# PCB.net
KiCad netlist of a schematic drawn in EAGLE
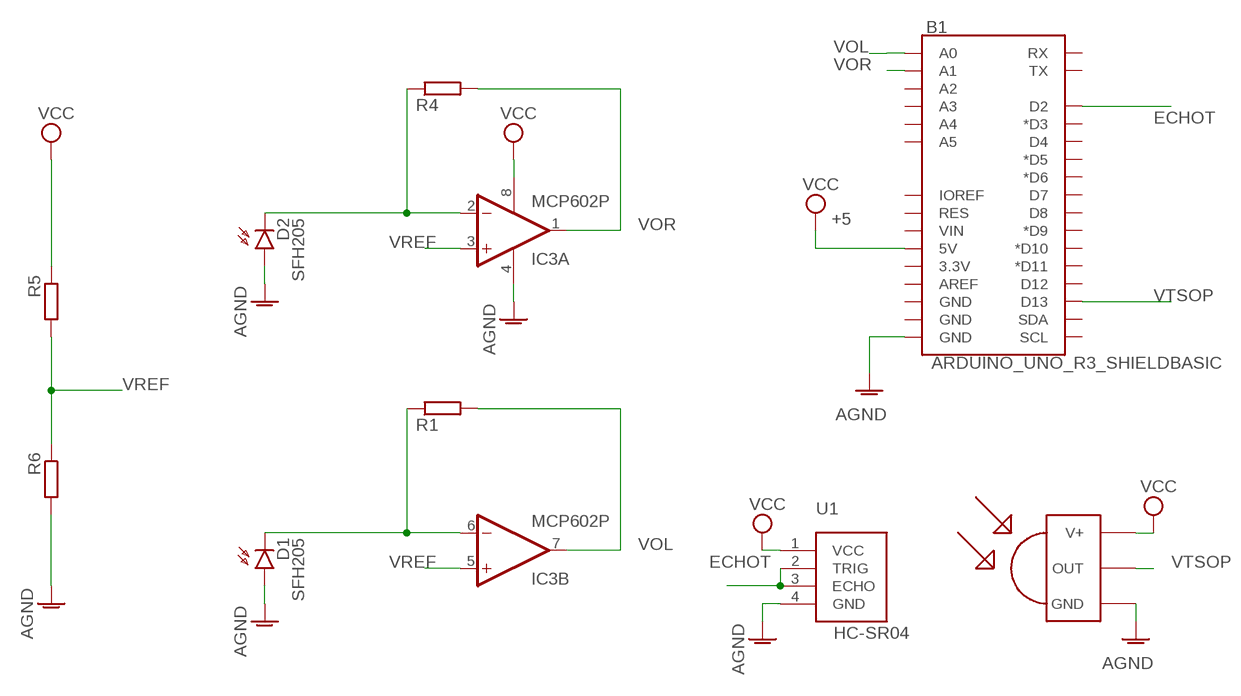
[diagram p0: schematic, sheet 1]

(export (version "E")
  (design (tool "Eeschema 10.0.6"))
  (components
    (comp (ref "B1")
      (value "ARDUINO_UNO_R3_SHIELDBASIC")
      (footprint "eagle-import:UNO_R3_SHIELD")
      (libsource (lib "eagle-import") (part "ARDUINO_UNO_R3_SHIELDBASIC"))
    )
    (comp (ref "D1")
      (value "SFH205")
      (footprint "eagle-import:SFH205")
      (libsource (lib "eagle-import") (part "SFH205"))
    )
    (comp (ref "D2")
      (value "SFH205")
      (footprint "eagle-import:SFH205")
      (libsource (lib "eagle-import") (part "SFH205"))
    )
    (comp (ref "IC3")
      (value "MCP602P")
      (footprint "eagle-import:DIL08")
      (libsource (lib "eagle-import") (part "MCP602P"))
    )
    (comp (ref "R1")
      (value "R-EU_0207/10")
      (footprint "eagle-import:0207_10")
      (libsource (lib "eagle-import") (part "R-EU_0207/10"))
    )
    (comp (ref "R4")
      (value "R-EU_0207/10")
      (footprint "eagle-import:0207_10")
      (libsource (lib "eagle-import") (part "R-EU_0207/10"))
    )
    (comp (ref "R5")
      (value "R-EU_0207/10")
      (footprint "eagle-import:0207_10")
      (libsource (lib "eagle-import") (part "R-EU_0207/10"))
    )
    (comp (ref "R6")
      (value "R-EU_0207/10")
      (footprint "eagle-import:0207_10")
      (libsource (lib "eagle-import") (part "R-EU_0207/10"))
    )
    (comp (ref "U$3")
      (value "TSOP4856")
      (footprint "eagle-import:TSOP18XX")
      (libsource (lib "eagle-import") (part "TSOP4856"))
    )
    (comp (ref "U1")
      (value "HC-SR04")
      (footprint "eagle-import:XCVR_HC-SR04")
      (fields (field (name "MF") "SparkFun Electronics"))
      (libsource (lib "eagle-import") (part "HC-SR04"))
    )
  )
  (nets
    (net (code "1") (name "/ECHOT") (class "Default")
      (node (ref "B1") (pin "D2") (pinfunction "D2_D2") (pintype "bidirectional"))
      (node (ref "U1") (pin "2") (pinfunction "TRIG_2") (pintype "bidirectional"))
      (node (ref "U1") (pin "3") (pinfunction "ECHO_3") (pintype "bidirectional"))
    )
    (net (code "2") (name "/VOL") (class "Default")
      (node (ref "B1") (pin "A0") (pinfunction "A0_A0") (pintype "bidirectional"))
      (node (ref "IC3") (pin "7") (pinfunction "OUT_7") (pintype "output"))
      (node (ref "R1") (pin "2") (pinfunction "2_2") (pintype "passive"))
    )
    (net (code "3") (name "/VOR") (class "Default")
      (node (ref "B1") (pin "A1") (pinfunction "A1_A1") (pintype "bidirectional"))
      (node (ref "IC3") (pin "1") (pinfunction "OUT_1") (pintype "output"))
      (node (ref "R4") (pin "2") (pinfunction "2_2") (pintype "passive"))
    )
    (net (code "4") (name "/VREF") (class "Default")
      (node (ref "IC3") (pin "3") (pinfunction "+IN_3") (pintype "input"))
      (node (ref "IC3") (pin "5") (pinfunction "+IN_5") (pintype "input"))
      (node (ref "R5") (pin "2") (pinfunction "2_2") (pintype "passive"))
      (node (ref "R6") (pin "1") (pinfunction "1_1") (pintype "passive"))
    )
    (net (code "5") (name "/VTSOP") (class "Default")
      (node (ref "B1") (pin "D13") (pinfunction "D13_D13") (pintype "bidirectional"))
      (node (ref "U$3") (pin "OUT") (pinfunction "OUT_OUT") (pintype "bidirectional"))
    )
    (net (code "6") (name "AGND") (class "Default")
      (node (ref "B1") (pin "GND@0") (pinfunction "GND_GND@0") (pintype "bidirectional"))
      (node (ref "D1") (pin "A") (pinfunction "A_A") (pintype "passive"))
      (node (ref "D2") (pin "A") (pinfunction "A_A") (pintype "passive"))
      (node (ref "IC3") (pin "4") (pinfunction "V-_4") (pintype "power_in"))
      (node (ref "R6") (pin "2") (pinfunction "2_2") (pintype "passive"))
      (node (ref "U$3") (pin "GND") (pinfunction "GND_GND") (pintype "bidirectional"))
      (node (ref "U1") (pin "4") (pinfunction "GND_4") (pintype "power_in"))
    )
    (net (code "7") (name "Net-(D1-C)") (class "Default")
      (node (ref "D1") (pin "K") (pinfunction "C_K") (pintype "passive"))
      (node (ref "IC3") (pin "6") (pinfunction "-IN_6") (pintype "input"))
      (node (ref "R1") (pin "1") (pinfunction "1_1") (pintype "passive"))
    )
    (net (code "8") (name "Net-(D2-C)") (class "Default")
      (node (ref "D2") (pin "K") (pinfunction "C_K") (pintype "passive"))
      (node (ref "IC3") (pin "2") (pinfunction "-IN_2") (pintype "input"))
      (node (ref "R4") (pin "1") (pinfunction "1_1") (pintype "passive"))
    )
    (net (code "9") (name "VCC") (class "Default")
      (node (ref "B1") (pin "5V") (pinfunction "5V_5V") (pintype "bidirectional"))
      (node (ref "IC3") (pin "8") (pinfunction "V+_8") (pintype "power_in"))
      (node (ref "R5") (pin "1") (pinfunction "1_1") (pintype "passive"))
      (node (ref "U$3") (pin "VCC") (pinfunction "V+_VCC") (pintype "bidirectional"))
      (node (ref "U1") (pin "1") (pinfunction "VCC_1") (pintype "power_in"))
    )
    (net (code "10") (name "unconnected-(B1-*D3-PadD3)") (class "Default")
      (node (ref "B1") (pin "D3") (pinfunction "*D3_D3") (pintype "bidirectional"))
    )
    (net (code "11") (name "unconnected-(B1-*D5-PadD5)") (class "Default")
      (node (ref "B1") (pin "D5") (pinfunction "*D5_D5") (pintype "bidirectional"))
    )
    (net (code "12") (name "unconnected-(B1-*D6-PadD6)") (class "Default")
      (node (ref "B1") (pin "D6") (pinfunction "*D6_D6") (pintype "bidirectional"))
    )
    (net (code "13") (name "unconnected-(B1-*D9-PadD9)") (class "Default")
      (node (ref "B1") (pin "D9") (pinfunction "*D9_D9") (pintype "bidirectional"))
    )
    (net (code "14") (name "unconnected-(B1-*D10-PadD10)") (class "Default")
      (node (ref "B1") (pin "D10") (pinfunction "*D10_D10") (pintype "bidirectional"))
    )
    (net (code "15") (name "unconnected-(B1-*D11-PadD11)") (class "Default")
      (node (ref "B1") (pin "D11") (pinfunction "*D11_D11") (pintype "bidirectional"))
    )
    (net (code "16") (name "unconnected-(B1-GND-PadGND@1)") (class "Default")
      (node (ref "B1") (pin "GND@1") (pinfunction "GND_GND@1") (pintype "bidirectional"))
    )
    (net (code "17") (name "unconnected-(B1-GND-PadGND@2)") (class "Default")
      (node (ref "B1") (pin "GND@2") (pinfunction "GND_GND@2") (pintype "bidirectional"))
    )
    (net (code "18") (name "unconnected-(B1-Pad3.3V)") (class "Default")
      (node (ref "B1") (pin "3.3V") (pinfunction "3.3V_3.3V") (pintype "bidirectional"))
    )
    (net (code "19") (name "unconnected-(B1-PadA2)") (class "Default")
      (node (ref "B1") (pin "A2") (pinfunction "A2_A2") (pintype "bidirectional"))
    )
    (net (code "20") (name "unconnected-(B1-PadA3)") (class "Default")
      (node (ref "B1") (pin "A3") (pinfunction "A3_A3") (pintype "bidirectional"))
    )
    (net (code "21") (name "unconnected-(B1-PadA4)") (class "Default")
      (node (ref "B1") (pin "A4") (pinfunction "A4_A4") (pintype "bidirectional"))
    )
    (net (code "22") (name "unconnected-(B1-PadA5)") (class "Default")
      (node (ref "B1") (pin "A5") (pinfunction "A5_A5") (pintype "bidirectional"))
    )
    (net (code "23") (name "unconnected-(B1-PadAREF)") (class "Default")
      (node (ref "B1") (pin "AREF") (pinfunction "AREF_AREF") (pintype "bidirectional"))
    )
    (net (code "24") (name "unconnected-(B1-PadD4)") (class "Default")
      (node (ref "B1") (pin "D4") (pinfunction "D4_D4") (pintype "bidirectional"))
    )
    (net (code "25") (name "unconnected-(B1-PadD7)") (class "Default")
      (node (ref "B1") (pin "D7") (pinfunction "D7_D7") (pintype "bidirectional"))
    )
    (net (code "26") (name "unconnected-(B1-PadD8)") (class "Default")
      (node (ref "B1") (pin "D8") (pinfunction "D8_D8") (pintype "bidirectional"))
    )
    (net (code "27") (name "unconnected-(B1-PadD12)") (class "Default")
      (node (ref "B1") (pin "D12") (pinfunction "D12_D12") (pintype "bidirectional"))
    )
    (net (code "28") (name "unconnected-(B1-PadIOREF)") (class "Default")
      (node (ref "B1") (pin "IOREF") (pinfunction "IOREF_IOREF") (pintype "bidirectional"))
    )
    (net (code "29") (name "unconnected-(B1-PadRES)") (class "Default")
      (node (ref "B1") (pin "RES") (pinfunction "RES_RES") (pintype "bidirectional"))
    )
    (net (code "30") (name "unconnected-(B1-PadRX)") (class "Default")
      (node (ref "B1") (pin "RX") (pinfunction "RX_RX") (pintype "bidirectional"))
    )
    (net (code "31") (name "unconnected-(B1-PadSCL)") (class "Default")
      (node (ref "B1") (pin "SCL") (pinfunction "SCL_SCL") (pintype "bidirectional"))
    )
    (net (code "32") (name "unconnected-(B1-PadSDA)") (class "Default")
      (node (ref "B1") (pin "SDA") (pinfunction "SDA_SDA") (pintype "bidirectional"))
    )
    (net (code "33") (name "unconnected-(B1-PadTX)") (class "Default")
      (node (ref "B1") (pin "TX") (pinfunction "TX_TX") (pintype "bidirectional"))
    )
    (net (code "34") (name "unconnected-(B1-PadVIN)") (class "Default")
      (node (ref "B1") (pin "VIN") (pinfunction "VIN_VIN") (pintype "bidirectional"))
    )
  )
)
